# SD_Card_Selection_Multiplexer.net
KiCad netlist of a schematic drawn in Altium Designer
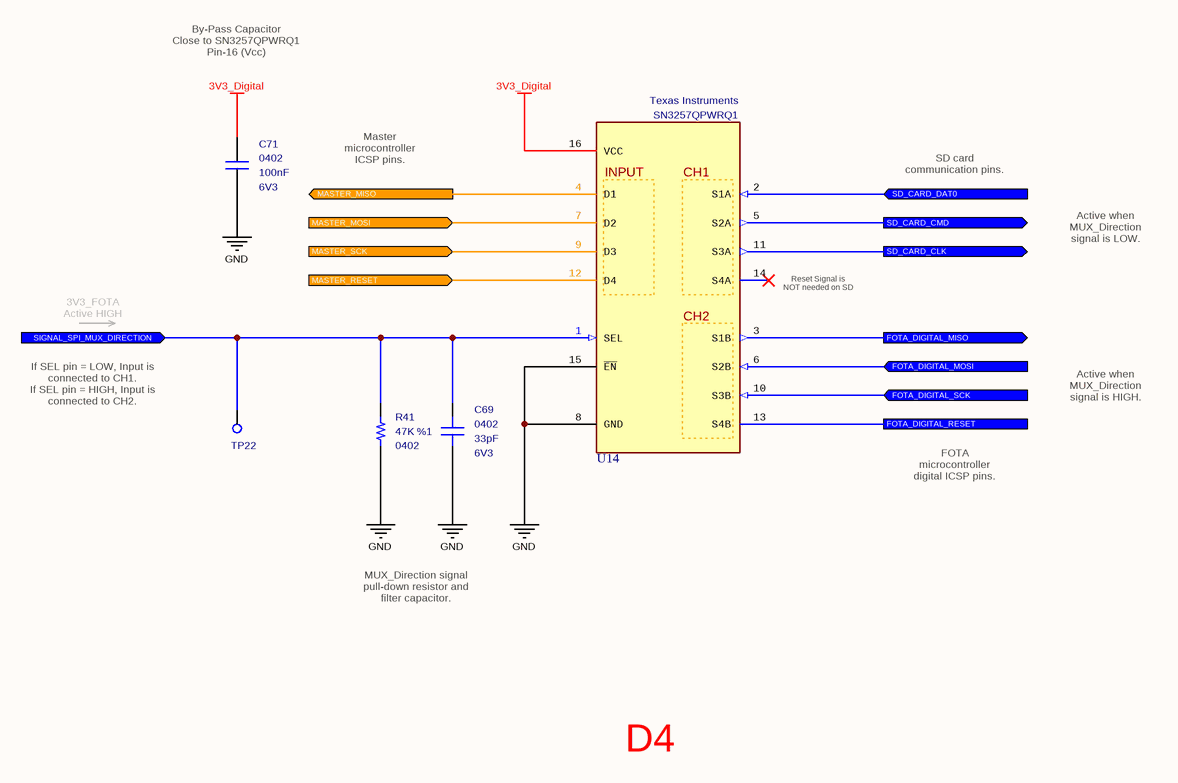
[diagram p0: SD Card Selection Multiplexer.SchDoc]

(export (version "E")
  (design (tool "Eeschema 10.0.6"))
  (components
    (comp (ref "C69")
      (value "33pF")
      (footprint "CAPACITOR_0402")
      (description "Capacitor - 33pF [0402] (Ceramic)")
      (fields
        (field (name "MANUFACTURER_PART_NUMBER") "C0402C330J9RACAUTO")
        (field (name "MOUSER_PART_NUMBER") "80-C0402C330J9RAUTO")
        (field (name "CASE") "0402")
        (field (name "VOLTAGE") "6V3")
      )
      (libsource (lib "Ovoo_Schematic") (part "Capacitor - 33pF [0402-6V3]"))
    )
    (comp (ref "C71")
      (value "100nF")
      (footprint "CAPACITOR_0402")
      (description "Capacitor - 100nF [0402-6V3] (Ceramic)")
      (fields
        (field (name "MANUFACTURER_PART_NUMBER") "04026D104KAT4A")
        (field (name "MOUSER_PART_NUMBER") "581-04026D104KAT4A")
        (field (name "CASE") "0402")
        (field (name "VOLTAGE") "6V3")
      )
      (libsource (lib "Ovoo_Schematic") (part "Capacitor - 100nF [0402-6V3]"))
    )
    (comp (ref "R41")
      (value "47K")
      (footprint "RESISTOR_0402")
      (description "Thick Film Resistors - SMD 1/16 W 47 Kohms 1%")
      (fields
        (field (name "MANUFACTURER_PART_NUMBER") "CRCW040247K0FKED")
        (field (name "MOUSER_PART_NUMBER") "71-CRCW0402-47K-E3")
        (field (name "TOLERANCE") "%1")
        (field (name "CASE") "0402")
      )
      (libsource (lib "Ovoo_Schematic") (part "Resistor - 47K"))
    )
    (comp (ref "TP22")
      (value "PCB - Test Point")
      (footprint "Test_Pad - Hole")
      (description "Test Point")
      (libsource (lib "Ovoo_Schematic") (part "PCB - Test Point"))
    )
    (comp (ref "U14")
      (value "SPI Switch IC")
      (footprint "TSSOP-16")
      (description "Analogue Switch ICs 2:1 (SPDT), 4-channel switch with 1.8-V logic 16-TSSOP -40 to 125")
      (fields
        (field (name "MOUSER PART NUMBER") "595-SN3257QPWRQ1")
        (field (name "MANUFACTURER_PART_NUMBER") "SN3257QPWRQ1")
        (field (name "MANUFACTURER_NAME") "Texas Instruments")
      )
      (libsource (lib "Ovoo_Schematic") (part "IC - SN3257QPWRQ1"))
    )
  )
  (nets
    (net (code "1") (name "/FOTA_DIGITAL_MISO") (class "Default")
      (node (ref "U14") (pin "3") (pinfunction "S1B_3") (pintype "output"))
    )
    (net (code "2") (name "/FOTA_DIGITAL_MOSI") (class "Default")
      (node (ref "U14") (pin "6") (pinfunction "S2B_6") (pintype "input"))
    )
    (net (code "3") (name "/FOTA_DIGITAL_RESET") (class "Default")
      (node (ref "U14") (pin "13") (pinfunction "S4B_13") (pintype "passive"))
    )
    (net (code "4") (name "/FOTA_DIGITAL_SCK") (class "Default")
      (node (ref "U14") (pin "10") (pinfunction "S3B_10") (pintype "input"))
    )
    (net (code "5") (name "/MASTER_MISO") (class "Default")
      (node (ref "U14") (pin "4") (pinfunction "D1_4") (pintype "passive"))
    )
    (net (code "6") (name "/MASTER_MOSI") (class "Default")
      (node (ref "U14") (pin "7") (pinfunction "D2_7") (pintype "passive"))
    )
    (net (code "7") (name "/MASTER_RESET") (class "Default")
      (node (ref "U14") (pin "12") (pinfunction "D4_12") (pintype "passive"))
    )
    (net (code "8") (name "/MASTER_SCK") (class "Default")
      (node (ref "U14") (pin "9") (pinfunction "D3_9") (pintype "passive"))
    )
    (net (code "9") (name "/SD_CARD_CLK") (class "Default")
      (node (ref "U14") (pin "11") (pinfunction "S3A_11") (pintype "output"))
    )
    (net (code "10") (name "/SD_CARD_CMD") (class "Default")
      (node (ref "U14") (pin "5") (pinfunction "S2A_5") (pintype "output"))
    )
    (net (code "11") (name "/SD_CARD_DAT0") (class "Default")
      (node (ref "U14") (pin "2") (pinfunction "S1A_2") (pintype "input"))
    )
    (net (code "12") (name "/SIGNAL_SPI_MUX_DIRECTION") (class "Default")
      (node (ref "C69") (pin "2") (pinfunction "2_2") (pintype "passive"))
      (node (ref "R41") (pin "2") (pinfunction "2_2") (pintype "passive"))
      (node (ref "TP22") (pin "1") (pinfunction "1_1") (pintype "passive"))
      (node (ref "U14") (pin "1") (pinfunction "SEL_1") (pintype "input"))
    )
    (net (code "13") (name "3V3_Digital") (class "Default")
      (node (ref "C71") (pin "1") (pinfunction "1_1") (pintype "passive"))
      (node (ref "U14") (pin "16") (pinfunction "VCC_16") (pintype "power_in"))
    )
    (net (code "14") (name "GND") (class "Default")
      (node (ref "C69") (pin "1") (pinfunction "1_1") (pintype "passive"))
      (node (ref "C71") (pin "2") (pinfunction "2_2") (pintype "passive"))
      (node (ref "R41") (pin "1") (pinfunction "1_1") (pintype "passive"))
      (node (ref "U14") (pin "15") (pinfunction "~{EN}_15") (pintype "power_in"))
      (node (ref "U14") (pin "8") (pinfunction "GND_8") (pintype "power_in"))
    )
    (net (code "15") (name "unconnected-(U14-S4A-Pad14)") (class "Default")
      (node (ref "U14") (pin "14") (pinfunction "S4A_14") (pintype "passive+no_connect"))
    )
  )
)
